# battery_protect.net
KiCad netlist of a schematic drawn in Altium Designer
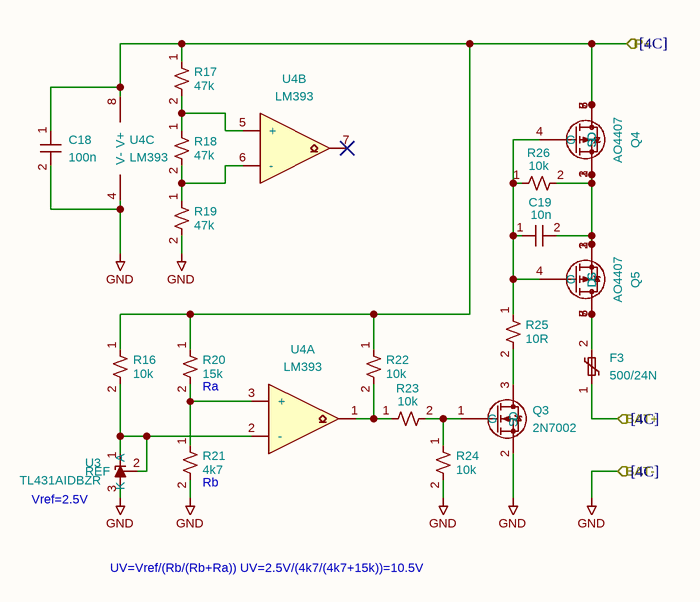
[diagram p0: battery_protect.SchDoc]

(export (version "E")
  (design (tool "Eeschema 10.0.6"))
  (components
    (comp (ref "C18")
      (value "100n")
      (footprint "C_0603_1608Metric")
      (libsource (lib "Device") (part "C_Small"))
    )
    (comp (ref "C19")
      (value "10n")
      (footprint "C_0603_1608Metric")
      (libsource (lib "Device") (part "C_Small"))
    )
    (comp (ref "F3")
      (value "500/24N")
      (footprint "Fuse_2920_7451Metric")
      (libsource (lib "Device") (part "Polyfuse_Small"))
    )
    (comp (ref "Q3") (value "2N7002") (footprint "SOT-23") (libsource (lib "Transistor_FET") (part "2N7002")))
    (comp (ref "Q4")
      (value "AO4407")
      (footprint "SOP-8_3.9x4.9mm_P1.27mm")
      (libsource (lib "Transistor_FET") (part "IRF7404"))
    )
    (comp (ref "Q5")
      (value "AO4407")
      (footprint "SOP-8_3.9x4.9mm_P1.27mm")
      (libsource (lib "Transistor_FET") (part "IRF7404"))
    )
    (comp (ref "R16")
      (value "10k")
      (footprint "R_0603_1608Metric")
      (libsource (lib "Device") (part "R_Small_US"))
    )
    (comp (ref "R17")
      (value "47k")
      (footprint "R_0603_1608Metric")
      (libsource (lib "Device") (part "R_Small_US"))
    )
    (comp (ref "R18")
      (value "47k")
      (footprint "R_0603_1608Metric")
      (libsource (lib "Device") (part "R_Small_US"))
    )
    (comp (ref "R19")
      (value "47k")
      (footprint "R_0603_1608Metric")
      (libsource (lib "Device") (part "R_Small_US"))
    )
    (comp (ref "R20")
      (value "15k")
      (footprint "R_0603_1608Metric")
      (libsource (lib "Device") (part "R_Small_US"))
    )
    (comp (ref "R21")
      (value "4k7")
      (footprint "R_0603_1608Metric")
      (libsource (lib "Device") (part "R_Small_US"))
    )
    (comp (ref "R22")
      (value "10k")
      (footprint "R_0603_1608Metric")
      (libsource (lib "Device") (part "R_Small_US"))
    )
    (comp (ref "R23")
      (value "10k")
      (footprint "R_0603_1608Metric")
      (libsource (lib "Device") (part "R_Small_US"))
    )
    (comp (ref "R24")
      (value "10k")
      (footprint "R_0603_1608Metric")
      (libsource (lib "Device") (part "R_Small_US"))
    )
    (comp (ref "R25")
      (value "10R")
      (footprint "R_0603_1608Metric")
      (libsource (lib "Device") (part "R_Small_US"))
    )
    (comp (ref "R26")
      (value "10k")
      (footprint "R_0603_1608Metric")
      (libsource (lib "Device") (part "R_Small_US"))
    )
    (comp (ref "U3")
      (value "TL431AIDBZR")
      (footprint "SOT-23")
      (libsource (lib "Reference_Voltage") (part "TL431DBZ"))
    )
    (comp (ref "U4")
      (value "LM393")
      (footprint "SOIC-8_3.9x4.9mm_P1.27mm")
      (libsource (lib "Comparator") (part "LM393"))
    )
  )
  (nets
    (net (code "1") (name "/BAT+") (class "Default")
      (node (ref "F3") (pin "1") (pinfunction "1_1") (pintype "passive"))
    )
    (net (code "2") (name "/P+") (class "Default")
      (node (ref "C18") (pin "1") (pinfunction "1_1") (pintype "passive"))
      (node (ref "Q4") (pin "5") (pinfunction "D_5") (pintype "passive"))
      (node (ref "Q4") (pin "6") (pinfunction "D_6") (pintype "passive"))
      (node (ref "Q4") (pin "7") (pinfunction "D_7") (pintype "passive"))
      (node (ref "Q4") (pin "8") (pinfunction "D_8") (pintype "passive"))
      (node (ref "R16") (pin "1") (pinfunction "1_1") (pintype "passive"))
      (node (ref "R17") (pin "1") (pinfunction "1_1") (pintype "passive"))
      (node (ref "R20") (pin "1") (pinfunction "1_1") (pintype "passive"))
      (node (ref "R22") (pin "1") (pinfunction "1_1") (pintype "passive"))
      (node (ref "U4") (pin "8") (pinfunction "V+_8") (pintype "passive"))
    )
    (net (code "3") (name "GND") (class "Default")
      (node (ref "C18") (pin "2") (pinfunction "2_2") (pintype "passive"))
      (node (ref "Q3") (pin "2") (pinfunction "S_2") (pintype "passive"))
      (node (ref "R19") (pin "2") (pinfunction "2_2") (pintype "passive"))
      (node (ref "R21") (pin "2") (pinfunction "2_2") (pintype "passive"))
      (node (ref "R24") (pin "2") (pinfunction "2_2") (pintype "passive"))
      (node (ref "U3") (pin "3") (pinfunction "A_3") (pintype "passive"))
      (node (ref "U4") (pin "4") (pinfunction "V-_4") (pintype "passive"))
    )
    (net (code "4") (name "Net-(C19-Pad2)") (class "Default")
      (node (ref "C19") (pin "2") (pinfunction "2_2") (pintype "passive"))
      (node (ref "Q4") (pin "1") (pinfunction "S_1") (pintype "passive"))
      (node (ref "Q4") (pin "2") (pinfunction "S_2") (pintype "passive"))
      (node (ref "Q4") (pin "3") (pinfunction "S_3") (pintype "passive"))
      (node (ref "Q5") (pin "1") (pinfunction "S_1") (pintype "passive"))
      (node (ref "Q5") (pin "2") (pinfunction "S_2") (pintype "passive"))
      (node (ref "Q5") (pin "3") (pinfunction "S_3") (pintype "passive"))
      (node (ref "R26") (pin "2") (pinfunction "2_2") (pintype "passive"))
    )
    (net (code "5") (name "Net-(F3-Pad2)") (class "Default")
      (node (ref "F3") (pin "2") (pinfunction "2_2") (pintype "passive"))
      (node (ref "Q5") (pin "5") (pinfunction "D_5") (pintype "passive"))
      (node (ref "Q5") (pin "6") (pinfunction "D_6") (pintype "passive"))
      (node (ref "Q5") (pin "7") (pinfunction "D_7") (pintype "passive"))
      (node (ref "Q5") (pin "8") (pinfunction "D_8") (pintype "passive"))
    )
    (net (code "6") (name "Net-(Q3-D)") (class "Default")
      (node (ref "Q3") (pin "3") (pinfunction "D_3") (pintype "passive"))
      (node (ref "R25") (pin "2") (pinfunction "2_2") (pintype "passive"))
    )
    (net (code "7") (name "Net-(Q3-G)") (class "Default")
      (node (ref "Q3") (pin "1") (pinfunction "G_1") (pintype "passive"))
      (node (ref "R23") (pin "2") (pinfunction "2_2") (pintype "passive"))
      (node (ref "R24") (pin "1") (pinfunction "1_1") (pintype "passive"))
    )
    (net (code "8") (name "Net-(Q4-G)") (class "Default")
      (node (ref "C19") (pin "1") (pinfunction "1_1") (pintype "passive"))
      (node (ref "Q4") (pin "4") (pinfunction "G_4") (pintype "passive"))
      (node (ref "Q5") (pin "4") (pinfunction "G_4") (pintype "passive"))
      (node (ref "R25") (pin "1") (pinfunction "1_1") (pintype "passive"))
      (node (ref "R26") (pin "1") (pinfunction "1_1") (pintype "passive"))
    )
    (net (code "9") (name "Net-(R22-Pad2)") (class "Default")
      (node (ref "R22") (pin "2") (pinfunction "2_2") (pintype "passive"))
      (node (ref "R23") (pin "1") (pinfunction "1_1") (pintype "passive"))
      (node (ref "U4") (pin "1") (pinfunction "1_1") (pintype "passive"))
    )
    (net (code "10") (name "Net-(U3-K)") (class "Default")
      (node (ref "R16") (pin "2") (pinfunction "2_2") (pintype "passive"))
      (node (ref "U3") (pin "1") (pinfunction "K_1") (pintype "passive"))
      (node (ref "U3") (pin "2") (pinfunction "REF_2") (pintype "passive"))
      (node (ref "U4") (pin "2") (pinfunction "-_2") (pintype "passive"))
    )
    (net (code "11") (name "Net-(U4A-+)") (class "Default")
      (node (ref "R20") (pin "2") (pinfunction "2_2") (pintype "passive"))
      (node (ref "R21") (pin "1") (pinfunction "1_1") (pintype "passive"))
      (node (ref "U4") (pin "3") (pinfunction "+_3") (pintype "passive"))
    )
    (net (code "12") (name "Net-(U4B-+)") (class "Default")
      (node (ref "R17") (pin "2") (pinfunction "2_2") (pintype "passive"))
      (node (ref "R18") (pin "1") (pinfunction "1_1") (pintype "passive"))
      (node (ref "U4") (pin "5") (pinfunction "+_5") (pintype "passive"))
    )
    (net (code "13") (name "Net-(U4B--)") (class "Default")
      (node (ref "R18") (pin "2") (pinfunction "2_2") (pintype "passive"))
      (node (ref "R19") (pin "1") (pinfunction "1_1") (pintype "passive"))
      (node (ref "U4") (pin "6") (pinfunction "-_6") (pintype "passive"))
    )
    (net (code "14") (name "unconnected-(U4-Pad7)") (class "Default")
      (node (ref "U4") (pin "7") (pinfunction "7_7") (pintype "passive+no_connect"))
    )
  )
)
